# Sheet2.net
KiCad netlist of a schematic drawn in Altium Designer
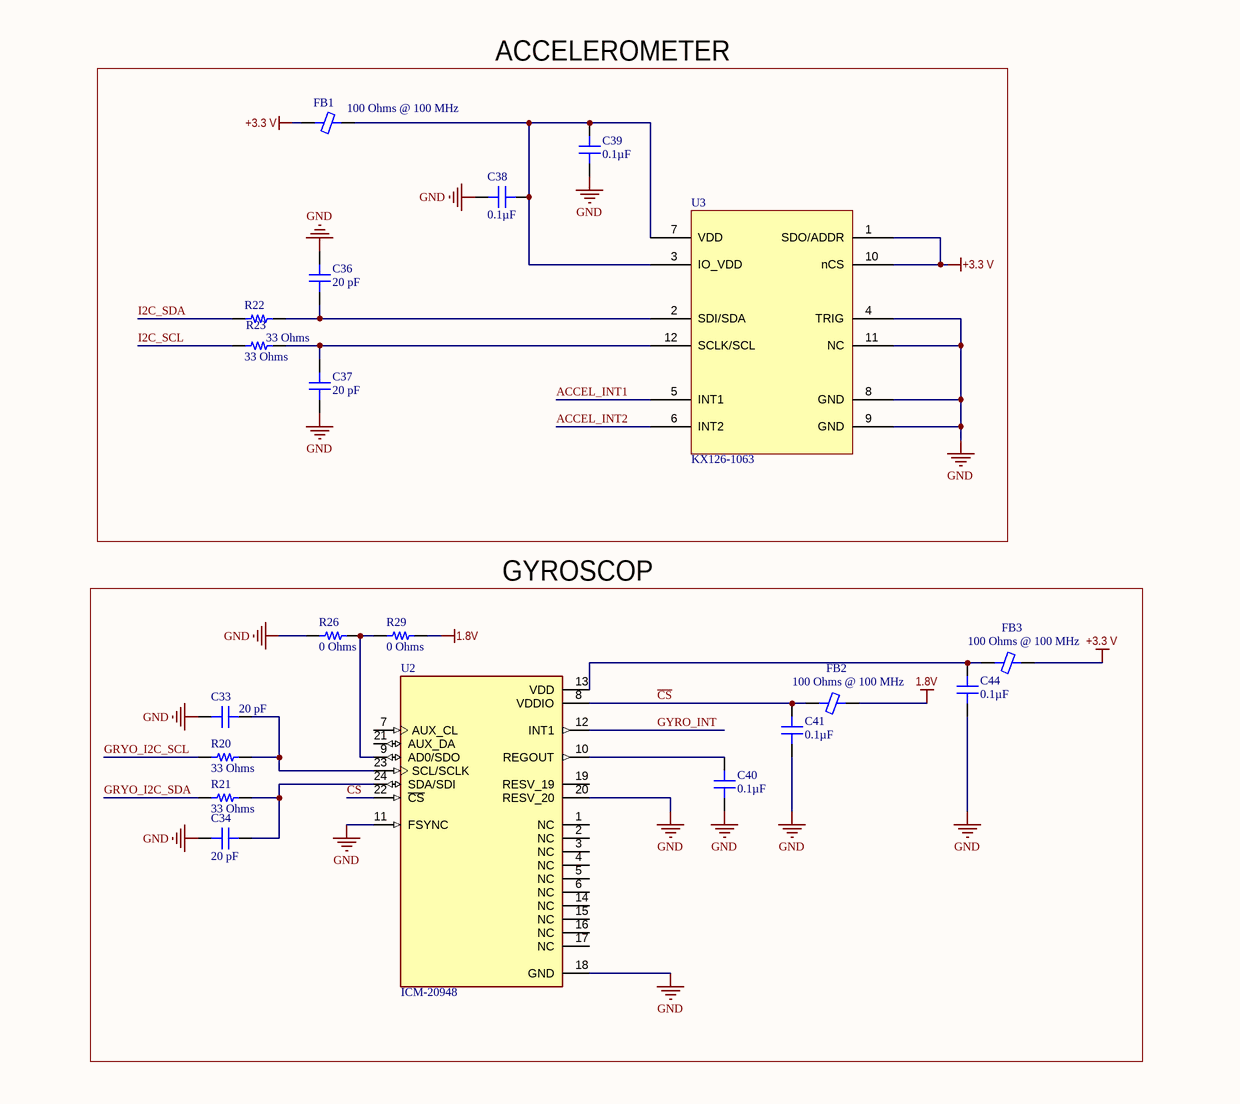
[diagram p0: Sheet2.SchDoc, top left]
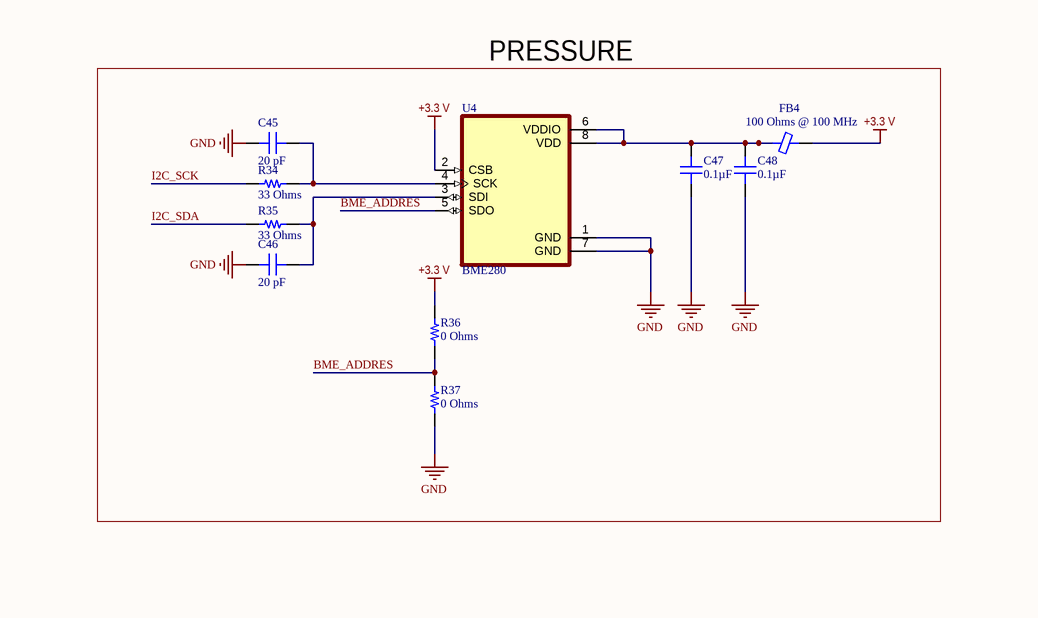
[diagram p1: Sheet2.SchDoc, top right]
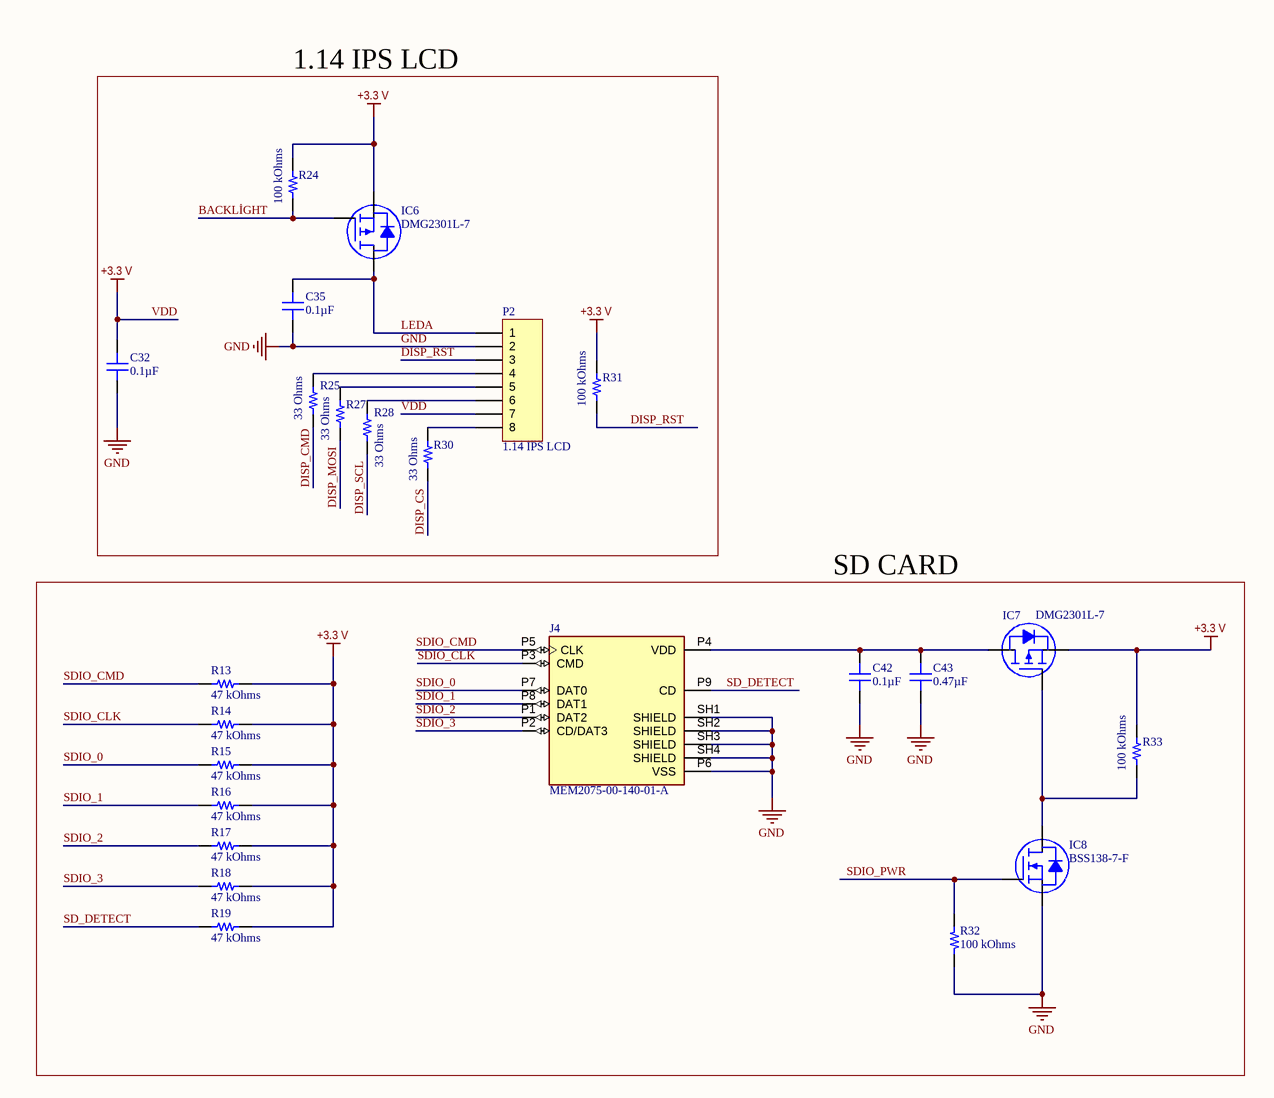
[diagram p2: Sheet2.SchDoc, bottom left]
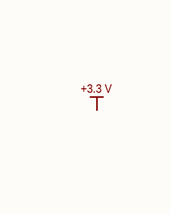
[diagram p3: Sheet2.SchDoc, bottom right]

(export (version "E")
  (design (tool "Eeschema 10.0.6"))
  (components
    (comp (ref "C32")
      (value "0.1µF")
      (footprint "CAP 0603_1608")
      (description "CAP CER 0.1UF 16V X5R 0603")
      (fields (field (name "PART NUMBER") "0603YD104KAT2A") (field (name "MANUFACTURER") "AVX Corporation"))
      (libsource (lib "Celestial Altium Library - altium_library") (part "Capacitor"))
    )
    (comp (ref "C33")
      (value "20 pF")
      (footprint "CAP 0603_1608")
      (description "CAP CER 20PF 25V NP0 0603")
      (fields (field (name "PART NUMBER") "C0603C200C3GAC7867") (field (name "MANUFACTURER") "KEMET"))
      (libsource (lib "Celestial Altium Library - altium_library") (part "Capacitor"))
    )
    (comp (ref "C34")
      (value "20 pF")
      (footprint "CAP 0603_1608")
      (description "CAP CER 20PF 25V NP0 0603")
      (fields (field (name "PART NUMBER") "C0603C200C3GAC7867") (field (name "MANUFACTURER") "KEMET"))
      (libsource (lib "Celestial Altium Library - altium_library") (part "Capacitor"))
    )
    (comp (ref "C35")
      (value "0.1µF")
      (footprint "CAP 0603_1608")
      (description "CAP CER 0.1UF 16V X5R 0603")
      (fields (field (name "PART NUMBER") "0603YD104KAT2A") (field (name "MANUFACTURER") "AVX Corporation"))
      (libsource (lib "Celestial Altium Library - altium_library") (part "Capacitor"))
    )
    (comp (ref "C36")
      (value "20 pF")
      (footprint "CAP 0603_1608")
      (description "CAP CER 20PF 25V NP0 0603")
      (fields (field (name "PART NUMBER") "C0603C200C3GAC7867") (field (name "MANUFACTURER") "KEMET"))
      (libsource (lib "Celestial Altium Library - altium_library") (part "Capacitor"))
    )
    (comp (ref "C37")
      (value "20 pF")
      (footprint "CAP 0603_1608")
      (description "CAP CER 20PF 25V NP0 0603")
      (fields (field (name "PART NUMBER") "C0603C200C3GAC7867") (field (name "MANUFACTURER") "KEMET"))
      (libsource (lib "Celestial Altium Library - altium_library") (part "Capacitor"))
    )
    (comp (ref "C38")
      (value "0.1µF")
      (footprint "CAP 0603_1608")
      (description "CAP CER 0.1UF 16V X5R 0603")
      (fields (field (name "PART NUMBER") "0603YD104KAT2A") (field (name "MANUFACTURER") "AVX Corporation"))
      (libsource (lib "Celestial Altium Library - altium_library") (part "Capacitor"))
    )
    (comp (ref "C39")
      (value "0.1µF")
      (footprint "CAP 0603_1608")
      (description "CAP CER 0.1UF 16V X5R 0603")
      (fields (field (name "PART NUMBER") "0603YD104KAT2A") (field (name "MANUFACTURER") "AVX Corporation"))
      (libsource (lib "Celestial Altium Library - altium_library") (part "Capacitor"))
    )
    (comp (ref "C40")
      (value "0.1µF")
      (footprint "CAP 0603_1608")
      (description "CAP CER 0.1UF 16V X5R 0603")
      (fields (field (name "PART NUMBER") "0603YD104KAT2A") (field (name "MANUFACTURER") "AVX Corporation"))
      (libsource (lib "Celestial Altium Library - altium_library") (part "Capacitor"))
    )
    (comp (ref "C41")
      (value "0.1µF")
      (footprint "CAP 0603_1608")
      (description "CAP CER 0.1UF 16V X5R 0603")
      (fields (field (name "PART NUMBER") "0603YD104KAT2A") (field (name "MANUFACTURER") "AVX Corporation"))
      (libsource (lib "Celestial Altium Library - altium_library") (part "Capacitor"))
    )
    (comp (ref "C42")
      (value "0.1µF")
      (footprint "CAP 0603_1608")
      (description "CAP CER 0.1UF 16V X5R 0603")
      (fields (field (name "PART NUMBER") "0603YD104KAT2A") (field (name "MANUFACTURER") "AVX Corporation"))
      (libsource (lib "Celestial Altium Library - altium_library") (part "Capacitor"))
    )
    (comp (ref "C43")
      (value "0.47µF")
      (footprint "CAP 0603_1608")
      (description "CAP CER 0.47UF 10V X5R 0603")
      (fields (field (name "PART NUMBER") "0603ZD474KAT2A") (field (name "MANUFACTURER") "AVX Corporation"))
      (libsource (lib "Celestial Altium Library - altium_library") (part "Capacitor"))
    )
    (comp (ref "C44")
      (value "0.1µF")
      (footprint "CAP 0603_1608")
      (description "CAP CER 0.1UF 16V X5R 0603")
      (fields (field (name "PART NUMBER") "0603YD104KAT2A") (field (name "MANUFACTURER") "AVX Corporation"))
      (libsource (lib "Celestial Altium Library - altium_library") (part "Capacitor"))
    )
    (comp (ref "C45")
      (value "20 pF")
      (footprint "CAP 0603_1608")
      (description "CAP CER 20PF 25V NP0 0603")
      (fields (field (name "PART NUMBER") "C0603C200C3GAC7867") (field (name "MANUFACTURER") "KEMET"))
      (libsource (lib "Celestial Altium Library - altium_library") (part "Capacitor"))
    )
    (comp (ref "C46")
      (value "20 pF")
      (footprint "CAP 0603_1608")
      (description "CAP CER 20PF 25V NP0 0603")
      (fields (field (name "PART NUMBER") "C0603C200C3GAC7867") (field (name "MANUFACTURER") "KEMET"))
      (libsource (lib "Celestial Altium Library - altium_library") (part "Capacitor"))
    )
    (comp (ref "C47")
      (value "0.1µF")
      (footprint "CAP 0603_1608")
      (description "CAP CER 0.1UF 16V X5R 0603")
      (fields (field (name "PART NUMBER") "0603YD104KAT2A") (field (name "MANUFACTURER") "AVX Corporation"))
      (libsource (lib "Celestial Altium Library - altium_library") (part "Capacitor"))
    )
    (comp (ref "C48")
      (value "0.1µF")
      (footprint "CAP 0603_1608")
      (description "CAP CER 0.1UF 16V X5R 0603")
      (fields (field (name "PART NUMBER") "0603YD104KAT2A") (field (name "MANUFACTURER") "AVX Corporation"))
      (libsource (lib "Celestial Altium Library - altium_library") (part "Capacitor"))
    )
    (comp (ref "FB1")
      (value "100 Ohms @ 100 MHz")
      (footprint "FER 0603_1608")
      (description "FERRITE BEAD 100 OHM 0603 1LN")
      (fields (field (name "PART NUMBER") "MH1608-101Y") (field (name "MANUFACTURER") "Bourns Inc."))
      (libsource (lib "Celestial Altium Library - altium_library") (part "Ferrite Chip"))
    )
    (comp (ref "FB2")
      (value "100 Ohms @ 100 MHz")
      (footprint "FER 0603_1608")
      (description "FERRITE BEAD 100 OHM 0603 1LN")
      (fields (field (name "PART NUMBER") "MH1608-101Y") (field (name "MANUFACTURER") "Bourns Inc."))
      (libsource (lib "Celestial Altium Library - altium_library") (part "Ferrite Chip"))
    )
    (comp (ref "FB3")
      (value "100 Ohms @ 100 MHz")
      (footprint "FER 0603_1608")
      (description "FERRITE BEAD 100 OHM 0603 1LN")
      (fields (field (name "PART NUMBER") "MH1608-101Y") (field (name "MANUFACTURER") "Bourns Inc."))
      (libsource (lib "Celestial Altium Library - altium_library") (part "Ferrite Chip"))
    )
    (comp (ref "FB4")
      (value "100 Ohms @ 100 MHz")
      (footprint "FER 0603_1608")
      (description "FERRITE BEAD 100 OHM 0603 1LN")
      (fields (field (name "PART NUMBER") "MH1608-101Y") (field (name "MANUFACTURER") "Bourns Inc."))
      (libsource (lib "Celestial Altium Library - altium_library") (part "Ferrite Chip"))
    )
    (comp (ref "IC6")
      (value "DMG2301L-7")
      (footprint "DIODES SOT-23-3")
      (description "MOSFET P-CH 20V 3A SOT23")
      (libsource (lib "Celestial Altium Library - altium_library") (part "DIODES MOSFET P-CH SOT-23-3"))
    )
    (comp (ref "IC7")
      (value "DMG2301L-7")
      (footprint "DIODES SOT-23-3")
      (description "MOSFET P-CH 20V 3A SOT23")
      (libsource (lib "") (part "DIODES MOSFET P-CH SOT-23-3_1"))
    )
    (comp (ref "IC8")
      (value "BSS138-7-F")
      (footprint "DIODES SOT-23-3")
      (description "MOSFET N-CH 50V 200MA SOT23-3")
      (libsource (lib "Celestial Altium Library - altium_library") (part "DIODES INC MOSFET N-CH SOT-23-3"))
    )
    (comp (ref "J4")
      (value "MEM2075-00-140-01-A")
      (footprint "GCT_MEM2075-00-140-01-A:GCT_MEM2075-00-140-01-A")
      (description "Micro SD Memory Card Connector, 1.4mm Profile SMT, Push-Push, with Normally open Switch")
      (libsource (lib "MEM2075-00-140-01-A") (part "MEM2075-00-140-01-A"))
    )
    (comp (ref "P2")
      (value "1.14 IPS LCD")
      (footprint "SnapEDApcb:HIROSE_FH52-8S-0.5SH(99)")
      (description "Header, 8-Pin")
      (fields (field (name "PUBLISHER") "Altium Limited"))
      (libsource (lib "Miscellaneous Connectors") (part "Header 8"))
    )
    (comp (ref "R13")
      (value "47 kOhms")
      (footprint "RES 0603_1608")
      (description "RES 47K OHM 5% 1/10W 0603")
      (fields
        (field (name "PART NUMBER") "CRGCQ0603J47K")
        (field (name "MANUFACTURER") "TE Connectivity Passive Product")
      )
      (libsource (lib "Celestial Altium Library - altium_library") (part "Resistor"))
    )
    (comp (ref "R14")
      (value "47 kOhms")
      (footprint "RES 0603_1608")
      (description "RES 47K OHM 5% 1/10W 0603")
      (fields
        (field (name "PART NUMBER") "CRGCQ0603J47K")
        (field (name "MANUFACTURER") "TE Connectivity Passive Product")
      )
      (libsource (lib "Celestial Altium Library - altium_library") (part "Resistor"))
    )
    (comp (ref "R15")
      (value "47 kOhms")
      (footprint "RES 0603_1608")
      (description "RES 47K OHM 5% 1/10W 0603")
      (fields
        (field (name "PART NUMBER") "CRGCQ0603J47K")
        (field (name "MANUFACTURER") "TE Connectivity Passive Product")
      )
      (libsource (lib "Celestial Altium Library - altium_library") (part "Resistor"))
    )
    (comp (ref "R16")
      (value "47 kOhms")
      (footprint "RES 0603_1608")
      (description "RES 47K OHM 5% 1/10W 0603")
      (fields
        (field (name "PART NUMBER") "CRGCQ0603J47K")
        (field (name "MANUFACTURER") "TE Connectivity Passive Product")
      )
      (libsource (lib "Celestial Altium Library - altium_library") (part "Resistor"))
    )
    (comp (ref "R17")
      (value "47 kOhms")
      (footprint "RES 0603_1608")
      (description "RES 47K OHM 5% 1/10W 0603")
      (fields
        (field (name "PART NUMBER") "CRGCQ0603J47K")
        (field (name "MANUFACTURER") "TE Connectivity Passive Product")
      )
      (libsource (lib "Celestial Altium Library - altium_library") (part "Resistor"))
    )
    (comp (ref "R18")
      (value "47 kOhms")
      (footprint "RES 0603_1608")
      (description "RES 47K OHM 5% 1/10W 0603")
      (fields
        (field (name "PART NUMBER") "CRGCQ0603J47K")
        (field (name "MANUFACTURER") "TE Connectivity Passive Product")
      )
      (libsource (lib "Celestial Altium Library - altium_library") (part "Resistor"))
    )
    (comp (ref "R19")
      (value "47 kOhms")
      (footprint "RES 0603_1608")
      (description "RES 47K OHM 5% 1/10W 0603")
      (fields
        (field (name "PART NUMBER") "CRGCQ0603J47K")
        (field (name "MANUFACTURER") "TE Connectivity Passive Product")
      )
      (libsource (lib "Celestial Altium Library - altium_library") (part "Resistor"))
    )
    (comp (ref "R20")
      (value "33 Ohms")
      (footprint "RES 0603_1608")
      (description "RES SMD 33 OHM 5% 1/10W 0603")
      (fields (field (name "PART NUMBER") "AC0603JR-0733RL") (field (name "MANUFACTURER") "Yageo"))
      (libsource (lib "Celestial Altium Library - altium_library") (part "Resistor"))
    )
    (comp (ref "R21")
      (value "33 Ohms")
      (footprint "RES 0603_1608")
      (description "RES SMD 33 OHM 5% 1/10W 0603")
      (fields (field (name "PART NUMBER") "AC0603JR-0733RL") (field (name "MANUFACTURER") "Yageo"))
      (libsource (lib "Celestial Altium Library - altium_library") (part "Resistor"))
    )
    (comp (ref "R22")
      (value "33 Ohms")
      (footprint "RES 0603_1608")
      (description "RES SMD 33 OHM 5% 1/10W 0603")
      (fields (field (name "PART NUMBER") "AC0603JR-0733RL") (field (name "MANUFACTURER") "Yageo"))
      (libsource (lib "Celestial Altium Library - altium_library") (part "Resistor"))
    )
    (comp (ref "R23")
      (value "33 Ohms")
      (footprint "RES 0603_1608")
      (description "RES SMD 33 OHM 5% 1/10W 0603")
      (fields (field (name "PART NUMBER") "AC0603JR-0733RL") (field (name "MANUFACTURER") "Yageo"))
      (libsource (lib "Celestial Altium Library - altium_library") (part "Resistor"))
    )
    (comp (ref "R24")
      (value "100 kOhms")
      (footprint "RES 0603_1608")
      (description "RES SMD 100K OHM 5% 1/10W 0603")
      (fields (field (name "PART NUMBER") "CRCW0603100KJNEA") (field (name "MANUFACTURER") "Vishay Dale"))
      (libsource (lib "Celestial Altium Library - altium_library") (part "Resistor"))
    )
    (comp (ref "R25")
      (value "33 Ohms")
      (footprint "RES 0603_1608")
      (description "RES SMD 33 OHM 5% 1/10W 0603")
      (fields (field (name "PART NUMBER") "AC0603JR-0733RL") (field (name "MANUFACTURER") "Yageo"))
      (libsource (lib "Celestial Altium Library - altium_library") (part "Resistor"))
    )
    (comp (ref "R26")
      (value "0 Ohms")
      (footprint "RES 0603_1608")
      (description "RES 0 OHM JUMPER 0603")
      (fields (field (name "PART NUMBER") "5111") (field (name "MANUFACTURER") "Keystone Electronics"))
      (libsource (lib "Celestial Altium Library - altium_library") (part "Resistor"))
    )
    (comp (ref "R27")
      (value "33 Ohms")
      (footprint "RES 0603_1608")
      (description "RES SMD 33 OHM 5% 1/10W 0603")
      (fields (field (name "PART NUMBER") "AC0603JR-0733RL") (field (name "MANUFACTURER") "Yageo"))
      (libsource (lib "Celestial Altium Library - altium_library") (part "Resistor"))
    )
    (comp (ref "R28")
      (value "33 Ohms")
      (footprint "RES 0603_1608")
      (description "RES SMD 33 OHM 5% 1/10W 0603")
      (fields (field (name "PART NUMBER") "AC0603JR-0733RL") (field (name "MANUFACTURER") "Yageo"))
      (libsource (lib "Celestial Altium Library - altium_library") (part "Resistor"))
    )
    (comp (ref "R29")
      (value "0 Ohms")
      (footprint "RES 0603_1608")
      (description "RES 0 OHM JUMPER 0603")
      (fields (field (name "PART NUMBER") "5111") (field (name "MANUFACTURER") "Keystone Electronics"))
      (libsource (lib "Celestial Altium Library - altium_library") (part "Resistor"))
    )
    (comp (ref "R30")
      (value "33 Ohms")
      (footprint "RES 0603_1608")
      (description "RES SMD 33 OHM 5% 1/10W 0603")
      (fields (field (name "PART NUMBER") "AC0603JR-0733RL") (field (name "MANUFACTURER") "Yageo"))
      (libsource (lib "Celestial Altium Library - altium_library") (part "Resistor"))
    )
    (comp (ref "R31")
      (value "100 kOhms")
      (footprint "RES 0603_1608")
      (description "RES SMD 100K OHM 5% 1/10W 0603")
      (fields (field (name "PART NUMBER") "CRCW0603100KJNEA") (field (name "MANUFACTURER") "Vishay Dale"))
      (libsource (lib "Celestial Altium Library - altium_library") (part "Resistor"))
    )
    (comp (ref "R32")
      (value "100 kOhms")
      (footprint "RES 0603_1608")
      (description "RES SMD 100K OHM 5% 1/10W 0603")
      (fields (field (name "PART NUMBER") "CRCW0603100KJNEA") (field (name "MANUFACTURER") "Vishay Dale"))
      (libsource (lib "Celestial Altium Library - altium_library") (part "Resistor"))
    )
    (comp (ref "R33")
      (value "100 kOhms")
      (footprint "RES 0603_1608")
      (description "RES SMD 100K OHM 5% 1/10W 0603")
      (fields (field (name "PART NUMBER") "CRCW0603100KJNEA") (field (name "MANUFACTURER") "Vishay Dale"))
      (libsource (lib "Celestial Altium Library - altium_library") (part "Resistor"))
    )
    (comp (ref "R34")
      (value "33 Ohms")
      (footprint "RES 0603_1608")
      (description "RES SMD 33 OHM 5% 1/10W 0603")
      (fields (field (name "PART NUMBER") "AC0603JR-0733RL") (field (name "MANUFACTURER") "Yageo"))
      (libsource (lib "Celestial Altium Library - altium_library") (part "Resistor"))
    )
    (comp (ref "R35")
      (value "33 Ohms")
      (footprint "RES 0603_1608")
      (description "RES SMD 33 OHM 5% 1/10W 0603")
      (fields (field (name "PART NUMBER") "AC0603JR-0733RL") (field (name "MANUFACTURER") "Yageo"))
      (libsource (lib "Celestial Altium Library - altium_library") (part "Resistor"))
    )
    (comp (ref "R36")
      (value "0 Ohms")
      (footprint "RES 0603_1608")
      (description "RES 0 OHM JUMPER 0603")
      (fields (field (name "PART NUMBER") "5111") (field (name "MANUFACTURER") "Keystone Electronics"))
      (libsource (lib "Celestial Altium Library - altium_library") (part "Resistor"))
    )
    (comp (ref "R37")
      (value "0 Ohms")
      (footprint "RES 0603_1608")
      (description "RES 0 OHM JUMPER 0603")
      (fields (field (name "PART NUMBER") "5111") (field (name "MANUFACTURER") "Keystone Electronics"))
      (libsource (lib "Celestial Altium Library - altium_library") (part "Resistor"))
    )
    (comp (ref "U2")
      (value "ICM-20948")
      (footprint "QFN40P300X300X105-24N:QFN40P300X300X105-24N")
      (description "Accelerometer, Gyroscope, Magnetometer, 9 Axis Sensor IÂ²C, SPI Output")
      (libsource (lib "ICM-20948") (part "ICM-20948"))
    )
    (comp (ref "U3")
      (value "KX126-1063")
      (footprint "KIONIX_KXTJ3-1057:KIONIX_KXTJ3-1057")
      (libsource (lib "KX126-1063") (part "KX126-1063"))
    )
    (comp (ref "U4")
      (value "BME280")
      (footprint "PSON65P250X250X100-8N:PSON65P250X250X100-8N")
      (libsource (lib "BME280") (part "BME280"))
    )
  )
  (nets
    (net (code "1") (name "+3.3 V") (class "Default")
      (node (ref "C32") (pin "2") (pinfunction "2_2") (pintype "passive"))
      (node (ref "FB1") (pin "2") (pinfunction "2_2") (pintype "passive"))
      (node (ref "FB3") (pin "2") (pinfunction "2_2") (pintype "passive"))
      (node (ref "FB4") (pin "2") (pinfunction "2_2") (pintype "passive"))
      (node (ref "IC6") (pin "2") (pinfunction "S_2") (pintype "passive"))
      (node (ref "IC7") (pin "2") (pinfunction "S_2") (pintype "passive"))
      (node (ref "P2") (pin "7") (pinfunction "7_7") (pintype "passive"))
      (node (ref "R13") (pin "2") (pinfunction "2_2") (pintype "passive"))
      (node (ref "R14") (pin "2") (pinfunction "2_2") (pintype "passive"))
      (node (ref "R15") (pin "2") (pinfunction "2_2") (pintype "passive"))
      (node (ref "R16") (pin "2") (pinfunction "2_2") (pintype "passive"))
      (node (ref "R17") (pin "2") (pinfunction "2_2") (pintype "passive"))
      (node (ref "R18") (pin "2") (pinfunction "2_2") (pintype "passive"))
      (node (ref "R19") (pin "2") (pinfunction "2_2") (pintype "passive"))
      (node (ref "R24") (pin "2") (pinfunction "2_2") (pintype "passive"))
      (node (ref "R31") (pin "2") (pinfunction "2_2") (pintype "passive"))
      (node (ref "R33") (pin "2") (pinfunction "2_2") (pintype "passive"))
      (node (ref "R36") (pin "2") (pinfunction "2_2") (pintype "passive"))
      (node (ref "U3") (pin "1") (pinfunction "SDO/ADDR_1") (pintype "passive"))
      (node (ref "U3") (pin "10") (pinfunction "nCS_10") (pintype "passive"))
      (node (ref "U4") (pin "2") (pinfunction "CSB_2") (pintype "input"))
    )
    (net (code "2") (name "/ACCEL_INT1") (class "Default")
      (node (ref "U3") (pin "5") (pinfunction "INT1_5") (pintype "passive"))
    )
    (net (code "3") (name "/ACCEL_INT2") (class "Default")
      (node (ref "U3") (pin "6") (pinfunction "INT2_6") (pintype "passive"))
    )
    (net (code "4") (name "/BACKLİGHT") (class "Default")
      (node (ref "IC6") (pin "1") (pinfunction "G_1") (pintype "passive"))
      (node (ref "R24") (pin "1") (pinfunction "1_1") (pintype "passive"))
    )
    (net (code "5") (name "/BME_ADDRES") (class "Default")
      (node (ref "R36") (pin "1") (pinfunction "1_1") (pintype "passive"))
      (node (ref "R37") (pin "2") (pinfunction "2_2") (pintype "passive"))
      (node (ref "U4") (pin "5") (pinfunction "SDO_5") (pintype "bidirectional"))
    )
    (net (code "6") (name "/DISP_CMD") (class "Default")
      (node (ref "R25") (pin "2") (pinfunction "2_2") (pintype "passive"))
    )
    (net (code "7") (name "/DISP_CS") (class "Default")
      (node (ref "R30") (pin "1") (pinfunction "1_1") (pintype "passive"))
    )
    (net (code "8") (name "/DISP_MOSI") (class "Default")
      (node (ref "R27") (pin "1") (pinfunction "1_1") (pintype "passive"))
    )
    (net (code "9") (name "/DISP_RST") (class "Default")
      (node (ref "P2") (pin "3") (pinfunction "3_3") (pintype "passive"))
      (node (ref "R31") (pin "1") (pinfunction "1_1") (pintype "passive"))
    )
    (net (code "10") (name "/DISP_SCL") (class "Default")
      (node (ref "R28") (pin "1") (pinfunction "1_1") (pintype "passive"))
    )
    (net (code "11") (name "/GRYO_I2C_SCL") (class "Default")
      (node (ref "R20") (pin "1") (pinfunction "1_1") (pintype "passive"))
    )
    (net (code "12") (name "/GRYO_I2C_SDA") (class "Default")
      (node (ref "R21") (pin "1") (pinfunction "1_1") (pintype "passive"))
    )
    (net (code "13") (name "/GYRO_INT") (class "Default")
      (node (ref "U2") (pin "12") (pinfunction "INT1_12") (pintype "output"))
    )
    (net (code "14") (name "/I2C_SCK") (class "Default")
      (node (ref "R34") (pin "2") (pinfunction "2_2") (pintype "passive"))
    )
    (net (code "15") (name "/I2C_SCL") (class "Default")
      (node (ref "R23") (pin "1") (pinfunction "1_1") (pintype "passive"))
    )
    (net (code "16") (name "/I2C_SDA") (class "Default")
      (node (ref "R22") (pin "1") (pinfunction "1_1") (pintype "passive"))
      (node (ref "R35") (pin "1") (pinfunction "1_1") (pintype "passive"))
    )
    (net (code "17") (name "/LEDA") (class "Default")
      (node (ref "C35") (pin "2") (pinfunction "2_2") (pintype "passive"))
      (node (ref "IC6") (pin "3") (pinfunction "D_3") (pintype "passive"))
      (node (ref "P2") (pin "1") (pinfunction "1_1") (pintype "passive"))
    )
    (net (code "18") (name "/SDIO_0") (class "Default")
      (node (ref "J4") (pin "P7") (pinfunction "DAT0_P7") (pintype "bidirectional"))
      (node (ref "R15") (pin "1") (pinfunction "1_1") (pintype "passive"))
    )
    (net (code "19") (name "/SDIO_1") (class "Default")
      (node (ref "J4") (pin "P8") (pinfunction "DAT1_P8") (pintype "bidirectional"))
      (node (ref "R16") (pin "1") (pinfunction "1_1") (pintype "passive"))
    )
    (net (code "20") (name "/SDIO_2") (class "Default")
      (node (ref "J4") (pin "P1") (pinfunction "DAT2_P1") (pintype "bidirectional"))
      (node (ref "R17") (pin "1") (pinfunction "1_1") (pintype "passive"))
    )
    (net (code "21") (name "/SDIO_3") (class "Default")
      (node (ref "J4") (pin "P2") (pinfunction "CD/DAT3_P2") (pintype "bidirectional"))
      (node (ref "R18") (pin "1") (pinfunction "1_1") (pintype "passive"))
    )
    (net (code "22") (name "/SDIO_CLK") (class "Default")
      (node (ref "J4") (pin "P3") (pinfunction "CMD_P3") (pintype "bidirectional"))
      (node (ref "R14") (pin "1") (pinfunction "1_1") (pintype "passive"))
    )
    (net (code "23") (name "/SDIO_CMD") (class "Default")
      (node (ref "J4") (pin "P5") (pinfunction "CLK_P5") (pintype "bidirectional"))
      (node (ref "R13") (pin "1") (pinfunction "1_1") (pintype "passive"))
    )
    (net (code "24") (name "/SDIO_PWR") (class "Default")
      (node (ref "IC8") (pin "1") (pinfunction "G_1") (pintype "passive"))
      (node (ref "R32") (pin "2") (pinfunction "2_2") (pintype "passive"))
    )
    (net (code "25") (name "/SD_DETECT") (class "Default")
      (node (ref "J4") (pin "P9") (pinfunction "CD_P9") (pintype "passive"))
      (node (ref "R19") (pin "1") (pinfunction "1_1") (pintype "passive"))
    )
    (net (code "26") (name "/~{CS}") (class "Default")
      (node (ref "C41") (pin "2") (pinfunction "2_2") (pintype "passive"))
      (node (ref "FB2") (pin "1") (pinfunction "1_1") (pintype "passive"))
      (node (ref "U2") (pin "22") (pinfunction "~{CS}_22") (pintype "input"))
      (node (ref "U2") (pin "8") (pinfunction "VDDIO_8") (pintype "power_in"))
    )
    (net (code "27") (name "1.8V") (class "Default")
      (node (ref "FB2") (pin "2") (pinfunction "2_2") (pintype "passive"))
      (node (ref "R29") (pin "2") (pinfunction "2_2") (pintype "passive"))
    )
    (net (code "28") (name "GND") (class "Default")
      (node (ref "C32") (pin "1") (pinfunction "1_1") (pintype "passive"))
      (node (ref "C33") (pin "1") (pinfunction "1_1") (pintype "passive"))
      (node (ref "C34") (pin "2") (pinfunction "2_2") (pintype "passive"))
      (node (ref "C35") (pin "1") (pinfunction "1_1") (pintype "passive"))
      (node (ref "C36") (pin "1") (pinfunction "1_1") (pintype "passive"))
      (node (ref "C37") (pin "2") (pinfunction "2_2") (pintype "passive"))
      (node (ref "C38") (pin "2") (pinfunction "2_2") (pintype "passive"))
      (node (ref "C39") (pin "1") (pinfunction "1_1") (pintype "passive"))
      (node (ref "C40") (pin "1") (pinfunction "1_1") (pintype "passive"))
      (node (ref "C41") (pin "1") (pinfunction "1_1") (pintype "passive"))
      (node (ref "C42") (pin "1") (pinfunction "1_1") (pintype "passive"))
      (node (ref "C43") (pin "1") (pinfunction "1_1") (pintype "passive"))
      (node (ref "C44") (pin "1") (pinfunction "1_1") (pintype "passive"))
      (node (ref "C45") (pin "1") (pinfunction "1_1") (pintype "passive"))
      (node (ref "C46") (pin "2") (pinfunction "2_2") (pintype "passive"))
      (node (ref "C47") (pin "1") (pinfunction "1_1") (pintype "passive"))
      (node (ref "C48") (pin "1") (pinfunction "1_1") (pintype "passive"))
      (node (ref "IC8") (pin "2") (pinfunction "S_2") (pintype "passive"))
      (node (ref "J4") (pin "P6") (pinfunction "VSS_P6") (pintype "power_in"))
      (node (ref "J4") (pin "SH1") (pinfunction "SHIELD_SH1") (pintype "power_in"))
      (node (ref "J4") (pin "SH2") (pinfunction "SHIELD_SH2") (pintype "power_in"))
      (node (ref "J4") (pin "SH3") (pinfunction "SHIELD_SH3") (pintype "power_in"))
      (node (ref "J4") (pin "SH4") (pinfunction "SHIELD_SH4") (pintype "power_in"))
      (node (ref "P2") (pin "2") (pinfunction "2_2") (pintype "passive"))
      (node (ref "R26") (pin "1") (pinfunction "1_1") (pintype "passive"))
      (node (ref "R32") (pin "1") (pinfunction "1_1") (pintype "passive"))
      (node (ref "R37") (pin "1") (pinfunction "1_1") (pintype "passive"))
      (node (ref "U2") (pin "11") (pinfunction "FSYNC_11") (pintype "input"))
      (node (ref "U2") (pin "18") (pinfunction "GND_18") (pintype "power_in"))
      (node (ref "U2") (pin "20") (pinfunction "RESV_20_20") (pintype "passive"))
      (node (ref "U3") (pin "11") (pinfunction "NC_11") (pintype "passive"))
      (node (ref "U3") (pin "4") (pinfunction "TRIG_4") (pintype "passive"))
      (node (ref "U3") (pin "8") (pinfunction "GND_8") (pintype "passive"))
      (node (ref "U3") (pin "9") (pinfunction "GND_9") (pintype "passive"))
      (node (ref "U4") (pin "1") (pinfunction "GND_1") (pintype "power_in"))
      (node (ref "U4") (pin "7") (pinfunction "GND_7") (pintype "power_in"))
    )
    (net (code "29") (name "Net-(IC7-D)") (class "Default")
      (node (ref "C42") (pin "2") (pinfunction "2_2") (pintype "passive"))
      (node (ref "C43") (pin "2") (pinfunction "2_2") (pintype "passive"))
      (node (ref "IC7") (pin "3") (pinfunction "D_3") (pintype "passive"))
      (node (ref "J4") (pin "P4") (pinfunction "VDD_P4") (pintype "power_in"))
    )
    (net (code "30") (name "Net-(IC7-G)") (class "Default")
      (node (ref "IC7") (pin "1") (pinfunction "G_1") (pintype "passive"))
      (node (ref "IC8") (pin "3") (pinfunction "D_3") (pintype "passive"))
      (node (ref "R33") (pin "1") (pinfunction "1_1") (pintype "passive"))
    )
    (net (code "31") (name "Net-(P2-Pad4)") (class "Default")
      (node (ref "P2") (pin "4") (pinfunction "4_4") (pintype "passive"))
      (node (ref "R25") (pin "1") (pinfunction "1_1") (pintype "passive"))
    )
    (net (code "32") (name "Net-(P2-Pad5)") (class "Default")
      (node (ref "P2") (pin "5") (pinfunction "5_5") (pintype "passive"))
      (node (ref "R27") (pin "2") (pinfunction "2_2") (pintype "passive"))
    )
    (net (code "33") (name "Net-(P2-Pad6)") (class "Default")
      (node (ref "P2") (pin "6") (pinfunction "6_6") (pintype "passive"))
      (node (ref "R28") (pin "2") (pinfunction "2_2") (pintype "passive"))
    )
    (net (code "34") (name "Net-(P2-Pad8)") (class "Default")
      (node (ref "P2") (pin "8") (pinfunction "8_8") (pintype "passive"))
      (node (ref "R30") (pin "2") (pinfunction "2_2") (pintype "passive"))
    )
    (net (code "35") (name "Net-(U2-AD0{slash}SDO)") (class "Default")
      (node (ref "R26") (pin "2") (pinfunction "2_2") (pintype "passive"))
      (node (ref "R29") (pin "1") (pinfunction "1_1") (pintype "passive"))
      (node (ref "U2") (pin "9") (pinfunction "AD0/SDO_9") (pintype "bidirectional"))
    )
    (net (code "36") (name "Net-(U2-REGOUT)") (class "Default")
      (node (ref "C40") (pin "2") (pinfunction "2_2") (pintype "passive"))
      (node (ref "U2") (pin "10") (pinfunction "REGOUT_10") (pintype "output"))
    )
    (net (code "37") (name "Net-(U2-SCL{slash}SCLK)") (class "Default")
      (node (ref "C33") (pin "2") (pinfunction "2_2") (pintype "passive"))
      (node (ref "R20") (pin "2") (pinfunction "2_2") (pintype "passive"))
      (node (ref "U2") (pin "23") (pinfunction "SCL/SCLK_23") (pintype "input"))
    )
    (net (code "38") (name "Net-(U2-SDA{slash}SDI)") (class "Default")
      (node (ref "C34") (pin "1") (pinfunction "1_1") (pintype "passive"))
      (node (ref "R21") (pin "2") (pinfunction "2_2") (pintype "passive"))
      (node (ref "U2") (pin "24") (pinfunction "SDA/SDI_24") (pintype "bidirectional"))
    )
    (net (code "39") (name "Net-(U2-VDD)") (class "Default")
      (node (ref "C44") (pin "2") (pinfunction "2_2") (pintype "passive"))
      (node (ref "FB3") (pin "1") (pinfunction "1_1") (pintype "passive"))
      (node (ref "U2") (pin "13") (pinfunction "VDD_13") (pintype "power_in"))
    )
    (net (code "40") (name "Net-(U3-IO_VDD)") (class "Default")
      (node (ref "C38") (pin "1") (pinfunction "1_1") (pintype "passive"))
      (node (ref "C39") (pin "2") (pinfunction "2_2") (pintype "passive"))
      (node (ref "FB1") (pin "1") (pinfunction "1_1") (pintype "passive"))
      (node (ref "U3") (pin "3") (pinfunction "IO_VDD_3") (pintype "passive"))
      (node (ref "U3") (pin "7") (pinfunction "VDD_7") (pintype "passive"))
    )
    (net (code "41") (name "Net-(U3-SCLK{slash}SCL)") (class "Default")
      (node (ref "C37") (pin "1") (pinfunction "1_1") (pintype "passive"))
      (node (ref "R23") (pin "2") (pinfunction "2_2") (pintype "passive"))
      (node (ref "U3") (pin "12") (pinfunction "SCLK/SCL_12") (pintype "passive"))
    )
    (net (code "42") (name "Net-(U3-SDI{slash}SDA)") (class "Default")
      (node (ref "C36") (pin "2") (pinfunction "2_2") (pintype "passive"))
      (node (ref "R22") (pin "2") (pinfunction "2_2") (pintype "passive"))
      (node (ref "U3") (pin "2") (pinfunction "SDI/SDA_2") (pintype "passive"))
    )
    (net (code "43") (name "Net-(U4-SCK)") (class "Default")
      (node (ref "C45") (pin "2") (pinfunction "2_2") (pintype "passive"))
      (node (ref "R34") (pin "1") (pinfunction "1_1") (pintype "passive"))
      (node (ref "U4") (pin "4") (pinfunction "SCK_4") (pintype "input"))
    )
    (net (code "44") (name "Net-(U4-SDI)") (class "Default")
      (node (ref "C46") (pin "1") (pinfunction "1_1") (pintype "passive"))
      (node (ref "R35") (pin "2") (pinfunction "2_2") (pintype "passive"))
      (node (ref "U4") (pin "3") (pinfunction "SDI_3") (pintype "bidirectional"))
    )
    (net (code "45") (name "Net-(U4-VDD)") (class "Default")
      (node (ref "C47") (pin "2") (pinfunction "2_2") (pintype "passive"))
      (node (ref "C48") (pin "2") (pinfunction "2_2") (pintype "passive"))
      (node (ref "FB4") (pin "1") (pinfunction "1_1") (pintype "passive"))
      (node (ref "U4") (pin "6") (pinfunction "VDDIO_6") (pintype "power_in"))
      (node (ref "U4") (pin "8") (pinfunction "VDD_8") (pintype "power_in"))
    )
    (net (code "46") (name "unconnected-(U2-AUX_CL-Pad7)") (class "Default")
      (node (ref "U2") (pin "7") (pinfunction "AUX_CL_7") (pintype "input"))
    )
    (net (code "47") (name "unconnected-(U2-AUX_DA-Pad21)") (class "Default")
      (node (ref "U2") (pin "21") (pinfunction "AUX_DA_21") (pintype "bidirectional"))
    )
    (net (code "48") (name "unconnected-(U2-NC-Pad1)") (class "Default")
      (node (ref "U2") (pin "1") (pinfunction "NC_1") (pintype "passive"))
    )
    (net (code "49") (name "unconnected-(U2-NC-Pad2)") (class "Default")
      (node (ref "U2") (pin "2") (pinfunction "NC_2") (pintype "passive"))
    )
    (net (code "50") (name "unconnected-(U2-NC-Pad3)") (class "Default")
      (node (ref "U2") (pin "3") (pinfunction "NC_3") (pintype "passive"))
    )
    (net (code "51") (name "unconnected-(U2-NC-Pad4)") (class "Default")
      (node (ref "U2") (pin "4") (pinfunction "NC_4") (pintype "passive"))
    )
    (net (code "52") (name "unconnected-(U2-NC-Pad5)") (class "Default")
      (node (ref "U2") (pin "5") (pinfunction "NC_5") (pintype "passive"))
    )
    (net (code "53") (name "unconnected-(U2-NC-Pad6)") (class "Default")
      (node (ref "U2") (pin "6") (pinfunction "NC_6") (pintype "passive"))
    )
    (net (code "54") (name "unconnected-(U2-NC-Pad14)") (class "Default")
      (node (ref "U2") (pin "14") (pinfunction "NC_14") (pintype "passive"))
    )
    (net (code "55") (name "unconnected-(U2-NC-Pad15)") (class "Default")
      (node (ref "U2") (pin "15") (pinfunction "NC_15") (pintype "passive"))
    )
    (net (code "56") (name "unconnected-(U2-NC-Pad16)") (class "Default")
      (node (ref "U2") (pin "16") (pinfunction "NC_16") (pintype "passive"))
    )
    (net (code "57") (name "unconnected-(U2-NC-Pad17)") (class "Default")
      (node (ref "U2") (pin "17") (pinfunction "NC_17") (pintype "passive"))
    )
    (net (code "58") (name "unconnected-(U2-RESV_19-Pad19)") (class "Default")
      (node (ref "U2") (pin "19") (pinfunction "RESV_19_19") (pintype "passive"))
    )
  )
)
